# ardustatversion10.net
KiCad netlist of a schematic drawn in EAGLE
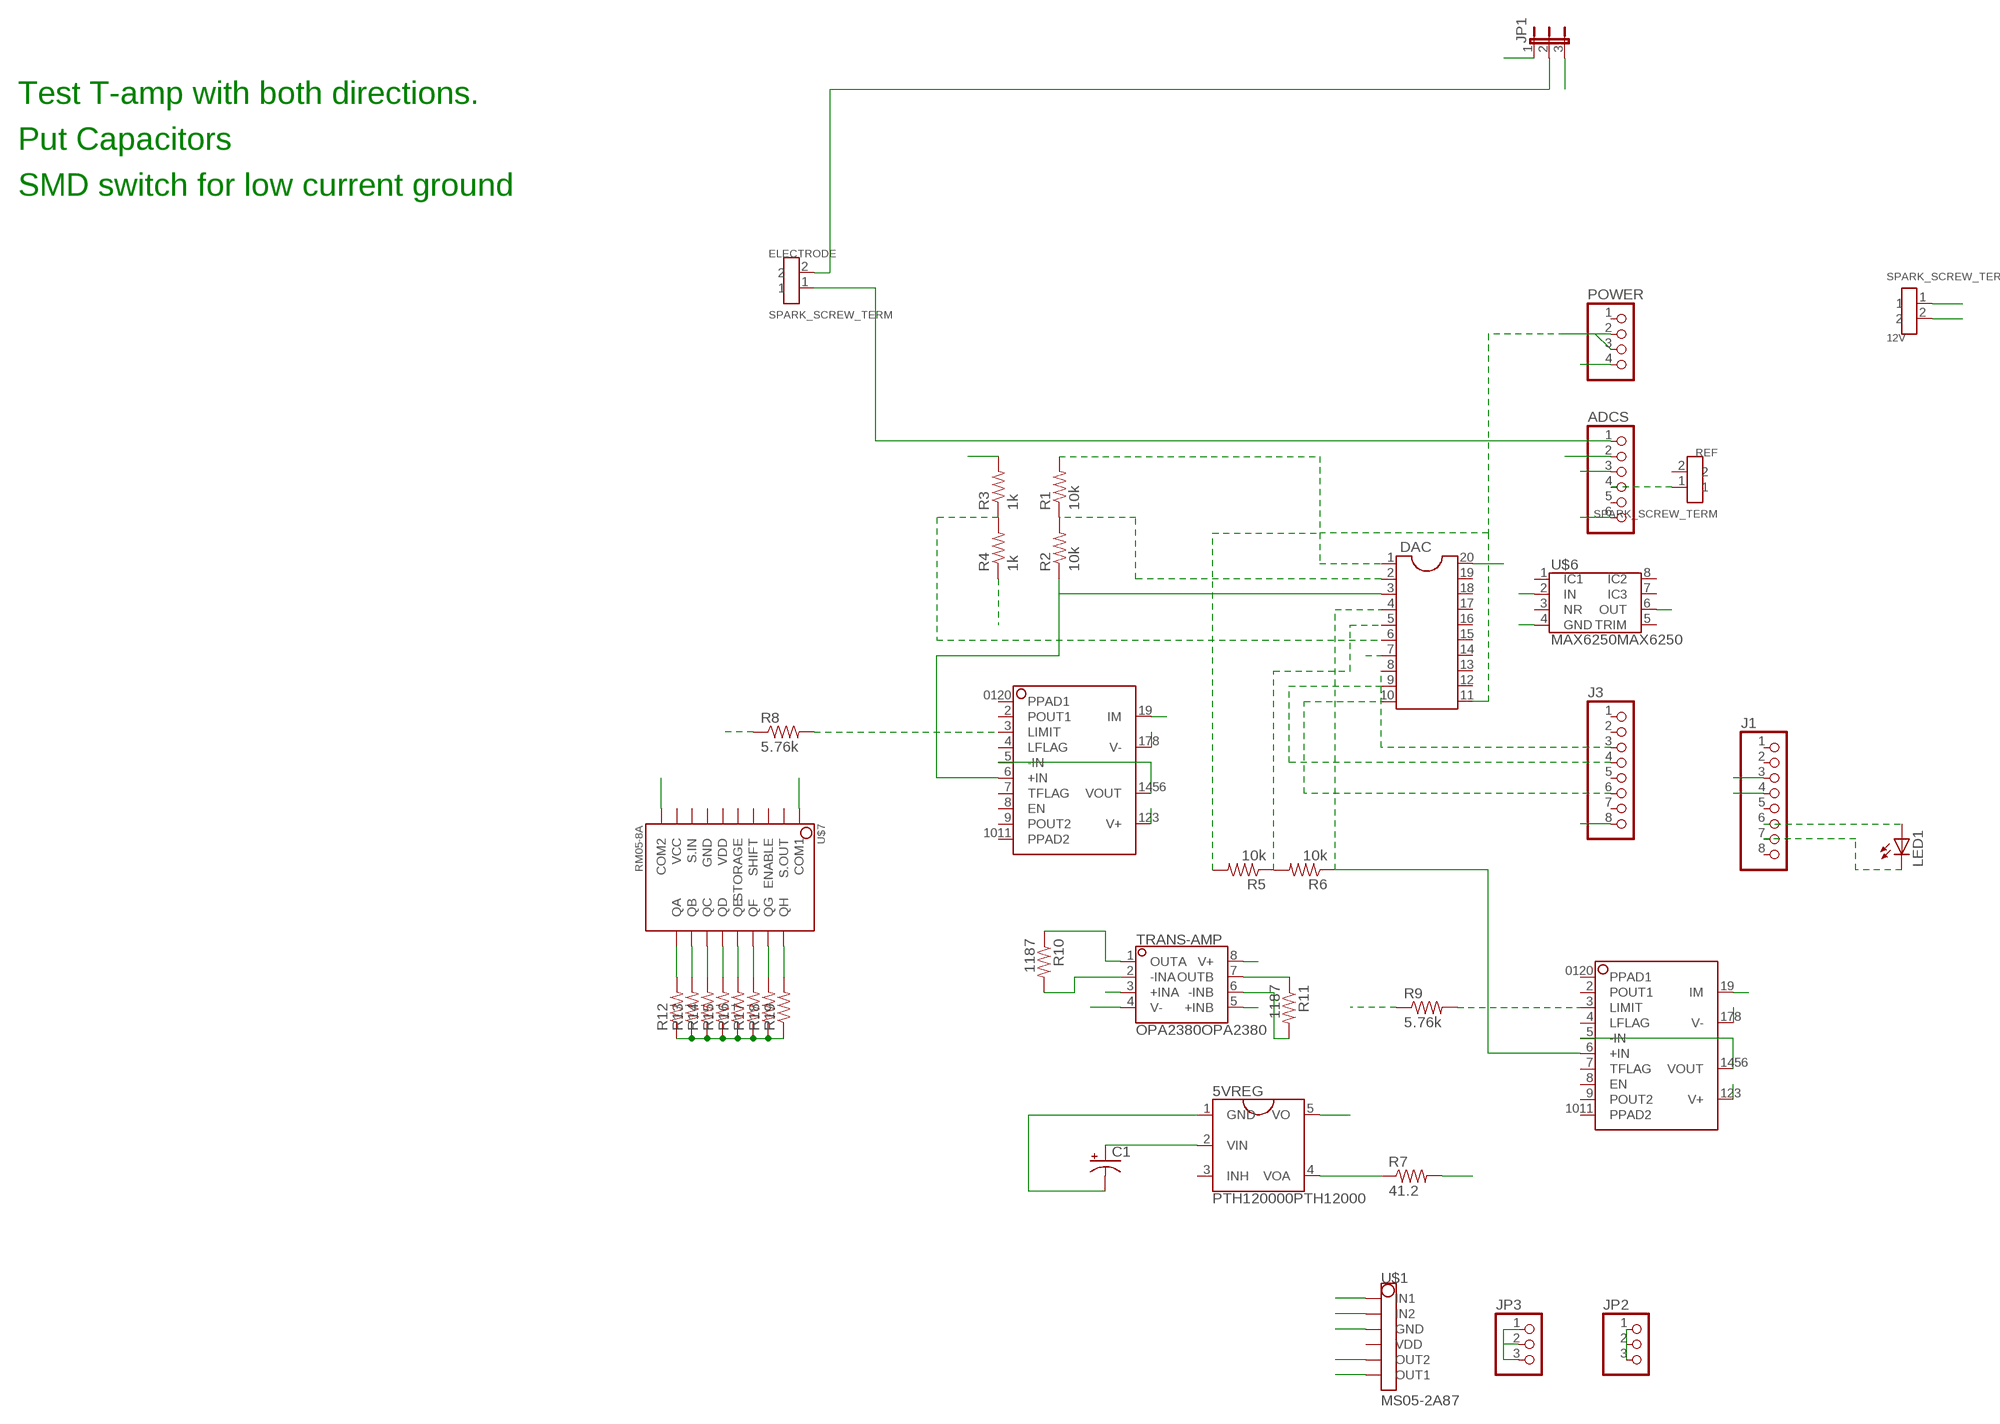
[diagram p0: schematic, sheet 1]

(export (version "E")
  (design (tool "Eeschema 10.0.6"))
  (components
    (comp (ref "5VREG")
      (value "PTH120000PTH12000")
      (footprint "eagle-import:PTH120000")
      (libsource (lib "eagle-import") (part "PTH120000PTH12000"))
    )
    (comp (ref "12V")
      (value "SPARK_SCREW_TERM")
      (footprint "eagle-import:SPARK_SCREW_TERM")
      (libsource (lib "eagle-import") (part "SPARK_SCREW_TERM"))
    )
    (comp (ref "ADCS")
      (value "PINHD-1X6")
      (footprint "eagle-import:1X06")
      (libsource (lib "eagle-import") (part "PINHD-1X6"))
    )
    (comp (ref "C1")
      (value "CPOL-USE5-10.5")
      (footprint "eagle-import:E5-10,5")
      (libsource (lib "eagle-import") (part "CPOL-USE5-10.5"))
    )
    (comp (ref "DAC")
      (value "DIL20S")
      (footprint "eagle-import:SOCKED-20")
      (libsource (lib "eagle-import") (part "DIL20S"))
    )
    (comp (ref "ELECTRODE")
      (value "SPARK_SCREW_TERM")
      (footprint "eagle-import:SPARK_SCREW_TERM")
      (libsource (lib "eagle-import") (part "SPARK_SCREW_TERM"))
    )
    (comp (ref "J1")
      (value "PINHD-1X8")
      (footprint "eagle-import:1X08")
      (libsource (lib "eagle-import") (part "PINHD-1X8"))
    )
    (comp (ref "J3")
      (value "PINHD-1X8")
      (footprint "eagle-import:1X08")
      (libsource (lib "eagle-import") (part "PINHD-1X8"))
    )
    (comp (ref "JP1")
      (value "JP2E")
      (footprint "eagle-import:JP2")
      (libsource (lib "eagle-import") (part "JP2E"))
    )
    (comp (ref "JP2")
      (value "PINHD-1X3")
      (footprint "eagle-import:1X03")
      (libsource (lib "eagle-import") (part "PINHD-1X3"))
    )
    (comp (ref "JP3")
      (value "PINHD-1X3")
      (footprint "eagle-import:1X03")
      (libsource (lib "eagle-import") (part "PINHD-1X3"))
    )
    (comp (ref "LED1")
      (value "LED5MM")
      (footprint "eagle-import:LED5MM")
      (libsource (lib "eagle-import") (part "LED5MM"))
    )
    (comp (ref "POWER")
      (value "PINHD-1X4")
      (footprint "eagle-import:1X04")
      (libsource (lib "eagle-import") (part "PINHD-1X4"))
    )
    (comp (ref "R1")
      (value "10k")
      (footprint "eagle-import:R1206")
      (libsource (lib "eagle-import") (part "R-US_R1206"))
    )
    (comp (ref "R2")
      (value "10k")
      (footprint "eagle-import:R1206")
      (libsource (lib "eagle-import") (part "resistor_R-US_R1206"))
    )
    (comp (ref "R3")
      (value "1k")
      (footprint "eagle-import:R1206")
      (libsource (lib "eagle-import") (part "R-US_R1206"))
    )
    (comp (ref "R4")
      (value "1k")
      (footprint "eagle-import:R1206")
      (libsource (lib "eagle-import") (part "R-US_R1206"))
    )
    (comp (ref "R5")
      (value "10k")
      (footprint "eagle-import:R1206")
      (libsource (lib "eagle-import") (part "R-US_R1206"))
    )
    (comp (ref "R6")
      (value "10k")
      (footprint "eagle-import:R1206")
      (libsource (lib "eagle-import") (part "R-US_R1206"))
    )
    (comp (ref "R7")
      (value "41.2")
      (footprint "eagle-import:M1206")
      (libsource (lib "eagle-import") (part "R-US_M1206"))
    )
    (comp (ref "R8")
      (value "5.76k")
      (footprint "eagle-import:R1206")
      (libsource (lib "eagle-import") (part "R-US_R1206"))
    )
    (comp (ref "R9")
      (value "5.76k")
      (footprint "eagle-import:M1206")
      (libsource (lib "eagle-import") (part "R-US_M1206"))
    )
    (comp (ref "R10")
      (value "1187")
      (footprint "eagle-import:M1206")
      (libsource (lib "eagle-import") (part "R-US_M1206"))
    )
    (comp (ref "R11")
      (value "1187")
      (footprint "eagle-import:M1206")
      (libsource (lib "eagle-import") (part "R-US_M1206"))
    )
    (comp (ref "R12")
      (value "R-US_0207/12")
      (footprint "eagle-import:0207_12")
      (libsource (lib "eagle-import") (part "resistor_R-US_0207/12"))
    )
    (comp (ref "R13")
      (value "R-US_0207/12")
      (footprint "eagle-import:0207_12")
      (libsource (lib "eagle-import") (part "resistor_R-US_0207/12"))
    )
    (comp (ref "R14")
      (value "R-US_0207/12")
      (footprint "eagle-import:0207_12")
      (libsource (lib "eagle-import") (part "resistor_R-US_0207/12"))
    )
    (comp (ref "R15")
      (value "R-US_0207/12")
      (footprint "eagle-import:0207_12")
      (libsource (lib "eagle-import") (part "resistor_R-US_0207/12"))
    )
    (comp (ref "R16")
      (value "R-US_0207/12")
      (footprint "eagle-import:0207_12")
      (libsource (lib "eagle-import") (part "resistor_R-US_0207/12"))
    )
    (comp (ref "R17")
      (value "R-US_0207/12")
      (footprint "eagle-import:0207_12")
      (libsource (lib "eagle-import") (part "resistor_R-US_0207/12"))
    )
    (comp (ref "R18")
      (value "R-US_0207/12")
      (footprint "eagle-import:0207_12")
      (libsource (lib "eagle-import") (part "resistor_R-US_0207/12"))
    )
    (comp (ref "R19")
      (value "R-US_0207/12")
      (footprint "eagle-import:0207_12")
      (libsource (lib "eagle-import") (part "resistor_R-US_0207/12"))
    )
    (comp (ref "REF")
      (value "SPARK_SCREW_TERM")
      (footprint "eagle-import:SPARK_SCREW_TERM")
      (libsource (lib "eagle-import") (part "SPARK_SCREW_TERM"))
    )
    (comp (ref "TRANS-AMP")
      (value "OPA2380OPA2380")
      (footprint "eagle-import:OPA2380")
      (libsource (lib "eagle-import") (part "OPA2380OPA2380"))
    )
    (comp (ref "U$1")
      (value "MS05-2A87")
      (footprint "eagle-import:MS05-2A87")
      (libsource (lib "eagle-import") (part "MS05-2A87"))
    )
    (comp (ref "U$3")
      (value "OPA569OPA569")
      (footprint "eagle-import:OPA569")
      (libsource (lib "eagle-import") (part "OPA569OPA569"))
    )
    (comp (ref "U$4")
      (value "OPA569OPA569")
      (footprint "eagle-import:OPA569")
      (libsource (lib "eagle-import") (part "OPA569OPA569"))
    )
    (comp (ref "U$6")
      (value "MAX6250MAX6250")
      (footprint "eagle-import:MAX6250")
      (libsource (lib "eagle-import") (part "MAX6250MAX6250"))
    )
    (comp (ref "U$7")
      (value "RM05-8A")
      (footprint "eagle-import:RM05-8A")
      (libsource (lib "eagle-import") (part "RM05-8A"))
    )
  )
  (nets
    (net (code "1") (name "/GND") (class "Default")
      (node (ref "12V") (pin "2") (pinfunction "2_2") (pintype "bidirectional"))
      (node (ref "5VREG") (pin "1") (pinfunction "GND_1") (pintype "power_in"))
      (node (ref "C1") (pin "-") (pinfunction "-_-") (pintype "passive"))
      (node (ref "DAC") (pin "1") (pinfunction "1_1") (pintype "passive"))
      (node (ref "DAC") (pin "11") (pinfunction "11_11") (pintype "passive"))
      (node (ref "JP1") (pin "3") (pinfunction "3_3") (pintype "passive"))
      (node (ref "POWER") (pin "2") (pinfunction "2_2") (pintype "passive"))
      (node (ref "POWER") (pin "3") (pinfunction "3_3") (pintype "passive"))
      (node (ref "R1") (pin "2") (pinfunction "2_2") (pintype "passive"))
      (node (ref "R4") (pin "1") (pinfunction "1_1") (pintype "passive"))
      (node (ref "R5") (pin "2") (pinfunction "2_2") (pintype "passive"))
      (node (ref "R7") (pin "2") (pinfunction "2_2") (pintype "passive"))
      (node (ref "R8") (pin "1") (pinfunction "1_1") (pintype "passive"))
      (node (ref "R9") (pin "1") (pinfunction "1_1") (pintype "passive"))
      (node (ref "TRANS-AMP") (pin "4") (pinfunction "V-_4") (pintype "power_in"))
      (node (ref "U$1") (pin "P$3") (pinfunction "GND_P$3") (pintype "bidirectional"))
      (node (ref "U$3") (pin "178") (pinfunction "V-_178") (pintype "bidirectional"))
      (node (ref "U$4") (pin "178") (pinfunction "V-_178") (pintype "bidirectional"))
      (node (ref "U$6") (pin "4") (pinfunction "GND_4") (pintype "bidirectional"))
    )
    (net (code "2") (name "/N$5") (class "Default")
      (node (ref "DAC") (pin "7") (pinfunction "7_7") (pintype "passive"))
      (node (ref "J1") (pin "3") (pinfunction "3_3") (pintype "passive"))
    )
    (net (code "3") (name "/N$8") (class "Default")
      (node (ref "ADCS") (pin "1") (pinfunction "1_1") (pintype "passive"))
      (node (ref "ELECTRODE") (pin "1") (pinfunction "1_1") (pintype "bidirectional"))
      (node (ref "JP2") (pin "1") (pinfunction "1_1") (pintype "passive"))
      (node (ref "JP2") (pin "2") (pinfunction "2_2") (pintype "passive"))
      (node (ref "JP2") (pin "3") (pinfunction "3_3") (pintype "passive"))
      (node (ref "R12") (pin "1") (pinfunction "1_1") (pintype "passive"))
      (node (ref "R13") (pin "1") (pinfunction "1_1") (pintype "passive"))
      (node (ref "R14") (pin "1") (pinfunction "1_1") (pintype "passive"))
      (node (ref "R15") (pin "1") (pinfunction "1_1") (pintype "passive"))
      (node (ref "R16") (pin "1") (pinfunction "1_1") (pintype "passive"))
      (node (ref "R17") (pin "1") (pinfunction "1_1") (pintype "passive"))
      (node (ref "R18") (pin "1") (pinfunction "1_1") (pintype "passive"))
      (node (ref "R19") (pin "1") (pinfunction "1_1") (pintype "passive"))
    )
    (net (code "4") (name "/N$9") (class "Default")
      (node (ref "U$1") (pin "P$2") (pinfunction "IN2_P$2") (pintype "bidirectional"))
      (node (ref "U$4") (pin "1456") (pinfunction "VOUT_1456") (pintype "bidirectional"))
      (node (ref "U$4") (pin "5") (pinfunction "-IN_5") (pintype "bidirectional"))
    )
    (net (code "5") (name "/N$10") (class "Default")
      (node (ref "R10") (pin "2") (pinfunction "2_2") (pintype "passive"))
      (node (ref "TRANS-AMP") (pin "2") (pinfunction "-INA_2") (pintype "input"))
      (node (ref "U$3") (pin "19") (pinfunction "IM_19") (pintype "bidirectional"))
    )
    (net (code "6") (name "/N$15") (class "Default")
      (node (ref "ADCS") (pin "2") (pinfunction "2_2") (pintype "passive"))
      (node (ref "DAC") (pin "3") (pinfunction "3_3") (pintype "passive"))
      (node (ref "R2") (pin "1") (pinfunction "1_1") (pintype "passive"))
      (node (ref "U$3") (pin "6") (pinfunction "+IN_6") (pintype "bidirectional"))
      (node (ref "U$7") (pin "P$1") (pinfunction "COM1_P$1") (pintype "bidirectional"))
      (node (ref "U$7") (pin "P$10") (pinfunction "COM2_P$10") (pintype "bidirectional"))
    )
    (net (code "7") (name "/N$19") (class "Default")
      (node (ref "5VREG") (pin "5") (pinfunction "VO_5") (pintype "bidirectional"))
      (node (ref "DAC") (pin "20") (pinfunction "20_20") (pintype "passive"))
      (node (ref "TRANS-AMP") (pin "8") (pinfunction "V+_8") (pintype "power_in"))
      (node (ref "U$3") (pin "123") (pinfunction "V+_123") (pintype "bidirectional"))
      (node (ref "U$4") (pin "123") (pinfunction "V+_123") (pintype "bidirectional"))
    )
    (net (code "8") (name "/N$21") (class "Default")
      (node (ref "ADCS") (pin "3") (pinfunction "3_3") (pintype "passive"))
      (node (ref "ELECTRODE") (pin "2") (pinfunction "2_2") (pintype "bidirectional"))
      (node (ref "JP1") (pin "2") (pinfunction "2_2") (pintype "passive"))
    )
    (net (code "9") (name "/N$22") (class "Default")
      (node (ref "12V") (pin "1") (pinfunction "1_1") (pintype "bidirectional"))
      (node (ref "5VREG") (pin "2") (pinfunction "VIN_2") (pintype "power_in"))
      (node (ref "C1") (pin "+") (pinfunction "+_+") (pintype "passive"))
      (node (ref "POWER") (pin "4") (pinfunction "4_4") (pintype "passive"))
      (node (ref "U$6") (pin "2") (pinfunction "IN_2") (pintype "bidirectional"))
    )
    (net (code "10") (name "/N$23") (class "Default")
      (node (ref "JP3") (pin "1") (pinfunction "1_1") (pintype "passive"))
      (node (ref "JP3") (pin "2") (pinfunction "2_2") (pintype "passive"))
      (node (ref "JP3") (pin "3") (pinfunction "3_3") (pintype "passive"))
      (node (ref "U$1") (pin "P$6") (pinfunction "OUT1_P$6") (pintype "bidirectional"))
    )
    (net (code "11") (name "/N$24") (class "Default")
      (node (ref "J3") (pin "8") (pinfunction "8_8") (pintype "passive"))
      (node (ref "R3") (pin "2") (pinfunction "2_2") (pintype "passive"))
      (node (ref "TRANS-AMP") (pin "3") (pinfunction "+INA_3") (pintype "input"))
      (node (ref "TRANS-AMP") (pin "5") (pinfunction "+INB_5") (pintype "input"))
      (node (ref "U$6") (pin "6") (pinfunction "OUT_6") (pintype "bidirectional"))
    )
    (net (code "12") (name "/N$26") (class "Default")
      (node (ref "U$1") (pin "P$1") (pinfunction "IN1_P$1") (pintype "bidirectional"))
      (node (ref "U$3") (pin "1456") (pinfunction "VOUT_1456") (pintype "bidirectional"))
      (node (ref "U$3") (pin "5") (pinfunction "-IN_5") (pintype "bidirectional"))
    )
    (net (code "13") (name "/N$36") (class "Default")
      (node (ref "JP1") (pin "1") (pinfunction "1_1") (pintype "passive"))
      (node (ref "U$1") (pin "P$5") (pinfunction "OUT2_P$5") (pintype "bidirectional"))
    )
    (net (code "14") (name "/N$48") (class "Default")
      (node (ref "ADCS") (pin "6") (pinfunction "6_6") (pintype "passive"))
      (node (ref "R11") (pin "1") (pinfunction "1_1") (pintype "passive"))
      (node (ref "TRANS-AMP") (pin "7") (pinfunction "OUTB_7") (pintype "output"))
    )
    (net (code "15") (name "/N$49") (class "Default")
      (node (ref "R11") (pin "2") (pinfunction "2_2") (pintype "passive"))
      (node (ref "TRANS-AMP") (pin "6") (pinfunction "-INB_6") (pintype "input"))
      (node (ref "U$4") (pin "19") (pinfunction "IM_19") (pintype "bidirectional"))
    )
    (net (code "16") (name "Net-(5VREG-VOA)") (class "Default")
      (node (ref "5VREG") (pin "4") (pinfunction "VOA_4") (pintype "input"))
      (node (ref "R7") (pin "1") (pinfunction "1_1") (pintype "passive"))
    )
    (net (code "17") (name "Net-(ADCS-Pad4)") (class "Default")
      (node (ref "ADCS") (pin "4") (pinfunction "4_4") (pintype "passive"))
      (node (ref "REF") (pin "1") (pinfunction "1_1") (pintype "bidirectional"))
    )
    (net (code "18") (name "Net-(DAC-Pad2)") (class "Default")
      (node (ref "DAC") (pin "2") (pinfunction "2_2") (pintype "passive"))
      (node (ref "R1") (pin "1") (pinfunction "1_1") (pintype "passive"))
      (node (ref "R2") (pin "2") (pinfunction "2_2") (pintype "passive"))
    )
    (net (code "19") (name "Net-(DAC-Pad5)") (class "Default")
      (node (ref "DAC") (pin "5") (pinfunction "5_5") (pintype "passive"))
      (node (ref "R5") (pin "1") (pinfunction "1_1") (pintype "passive"))
      (node (ref "R6") (pin "2") (pinfunction "2_2") (pintype "passive"))
    )
    (net (code "20") (name "Net-(DAC-Pad6)") (class "Default")
      (node (ref "DAC") (pin "6") (pinfunction "6_6") (pintype "passive"))
      (node (ref "R3") (pin "1") (pinfunction "1_1") (pintype "passive"))
      (node (ref "R4") (pin "2") (pinfunction "2_2") (pintype "passive"))
    )
    (net (code "21") (name "Net-(DAC-Pad8)") (class "Default")
      (node (ref "DAC") (pin "8") (pinfunction "8_8") (pintype "passive"))
      (node (ref "J3") (pin "3") (pinfunction "3_3") (pintype "passive"))
    )
    (net (code "22") (name "Net-(DAC-Pad9)") (class "Default")
      (node (ref "DAC") (pin "9") (pinfunction "9_9") (pintype "passive"))
      (node (ref "J3") (pin "4") (pinfunction "4_4") (pintype "passive"))
    )
    (net (code "23") (name "Net-(DAC-Pad10)") (class "Default")
      (node (ref "DAC") (pin "10") (pinfunction "10_10") (pintype "passive"))
      (node (ref "J3") (pin "6") (pinfunction "6_6") (pintype "passive"))
    )
    (net (code "24") (name "Net-(J1-Pad6)") (class "Default")
      (node (ref "J1") (pin "6") (pinfunction "6_6") (pintype "passive"))
      (node (ref "LED1") (pin "A") (pinfunction "A_A") (pintype "passive"))
    )
    (net (code "25") (name "Net-(LED1-C)") (class "Default")
      (node (ref "J1") (pin "7") (pinfunction "7_7") (pintype "passive"))
      (node (ref "LED1") (pin "K") (pinfunction "C_K") (pintype "passive"))
    )
    (net (code "26") (name "Net-(TRANS-AMP-OUTA)") (class "Default")
      (node (ref "R10") (pin "1") (pinfunction "1_1") (pintype "passive"))
      (node (ref "TRANS-AMP") (pin "1") (pinfunction "OUTA_1") (pintype "output"))
    )
    (net (code "27") (name "Net-(U$3-LIMIT)") (class "Default")
      (node (ref "R8") (pin "2") (pinfunction "2_2") (pintype "passive"))
      (node (ref "U$3") (pin "3") (pinfunction "LIMIT_3") (pintype "bidirectional"))
    )
    (net (code "28") (name "Net-(U$4-+IN)") (class "Default")
      (node (ref "DAC") (pin "4") (pinfunction "4_4") (pintype "passive"))
      (node (ref "R6") (pin "1") (pinfunction "1_1") (pintype "passive"))
      (node (ref "U$4") (pin "6") (pinfunction "+IN_6") (pintype "bidirectional"))
    )
    (net (code "29") (name "Net-(U$4-LIMIT)") (class "Default")
      (node (ref "R9") (pin "2") (pinfunction "2_2") (pintype "passive"))
      (node (ref "U$4") (pin "3") (pinfunction "LIMIT_3") (pintype "bidirectional"))
    )
    (net (code "30") (name "Net-(U$7-QA)") (class "Default")
      (node (ref "R12") (pin "2") (pinfunction "2_2") (pintype "passive"))
      (node (ref "U$7") (pin "P$11") (pinfunction "QA_P$11") (pintype "bidirectional"))
    )
    (net (code "31") (name "Net-(U$7-QB)") (class "Default")
      (node (ref "R13") (pin "2") (pinfunction "2_2") (pintype "passive"))
      (node (ref "U$7") (pin "P$12") (pinfunction "QB_P$12") (pintype "bidirectional"))
    )
    (net (code "32") (name "Net-(U$7-QC)") (class "Default")
      (node (ref "R14") (pin "2") (pinfunction "2_2") (pintype "passive"))
      (node (ref "U$7") (pin "P$13") (pinfunction "QC_P$13") (pintype "bidirectional"))
    )
    (net (code "33") (name "Net-(U$7-QD)") (class "Default")
      (node (ref "R15") (pin "2") (pinfunction "2_2") (pintype "passive"))
      (node (ref "U$7") (pin "P$14") (pinfunction "QD_P$14") (pintype "bidirectional"))
    )
    (net (code "34") (name "Net-(U$7-QE)") (class "Default")
      (node (ref "R16") (pin "2") (pinfunction "2_2") (pintype "passive"))
      (node (ref "U$7") (pin "P$15") (pinfunction "QE_P$15") (pintype "bidirectional"))
    )
    (net (code "35") (name "Net-(U$7-QF)") (class "Default")
      (node (ref "R17") (pin "2") (pinfunction "2_2") (pintype "passive"))
      (node (ref "U$7") (pin "P$16") (pinfunction "QF_P$16") (pintype "bidirectional"))
    )
    (net (code "36") (name "Net-(U$7-QG)") (class "Default")
      (node (ref "R18") (pin "2") (pinfunction "2_2") (pintype "passive"))
      (node (ref "U$7") (pin "P$17") (pinfunction "QG_P$17") (pintype "bidirectional"))
    )
    (net (code "37") (name "Net-(U$7-QH)") (class "Default")
      (node (ref "R19") (pin "2") (pinfunction "2_2") (pintype "passive"))
      (node (ref "U$7") (pin "P$18") (pinfunction "QH_P$18") (pintype "bidirectional"))
    )
    (net (code "38") (name "unconnected-(5VREG-INH-Pad3)") (class "Default")
      (node (ref "5VREG") (pin "3") (pinfunction "INH_3") (pintype "input"))
    )
    (net (code "39") (name "unconnected-(ADCS-Pad5)") (class "Default")
      (node (ref "ADCS") (pin "5") (pinfunction "5_5") (pintype "passive"))
    )
    (net (code "40") (name "unconnected-(DAC-Pad12)") (class "Default")
      (node (ref "DAC") (pin "12") (pinfunction "12_12") (pintype "passive"))
    )
    (net (code "41") (name "unconnected-(DAC-Pad13)") (class "Default")
      (node (ref "DAC") (pin "13") (pinfunction "13_13") (pintype "passive"))
    )
    (net (code "42") (name "unconnected-(DAC-Pad14)") (class "Default")
      (node (ref "DAC") (pin "14") (pinfunction "14_14") (pintype "passive"))
    )
    (net (code "43") (name "unconnected-(DAC-Pad15)") (class "Default")
      (node (ref "DAC") (pin "15") (pinfunction "15_15") (pintype "passive"))
    )
    (net (code "44") (name "unconnected-(DAC-Pad16)") (class "Default")
      (node (ref "DAC") (pin "16") (pinfunction "16_16") (pintype "passive"))
    )
    (net (code "45") (name "unconnected-(DAC-Pad17)") (class "Default")
      (node (ref "DAC") (pin "17") (pinfunction "17_17") (pintype "passive"))
    )
    (net (code "46") (name "unconnected-(DAC-Pad18)") (class "Default")
      (node (ref "DAC") (pin "18") (pinfunction "18_18") (pintype "passive"))
    )
    (net (code "47") (name "unconnected-(DAC-Pad19)") (class "Default")
      (node (ref "DAC") (pin "19") (pinfunction "19_19") (pintype "passive"))
    )
    (net (code "48") (name "unconnected-(J1-Pad1)") (class "Default")
      (node (ref "J1") (pin "1") (pinfunction "1_1") (pintype "passive"))
    )
    (net (code "49") (name "unconnected-(J1-Pad2)") (class "Default")
      (node (ref "J1") (pin "2") (pinfunction "2_2") (pintype "passive"))
    )
    (net (code "50") (name "unconnected-(J1-Pad4)") (class "Default")
      (node (ref "J1") (pin "4") (pinfunction "4_4") (pintype "passive"))
    )
    (net (code "51") (name "unconnected-(J1-Pad5)") (class "Default")
      (node (ref "J1") (pin "5") (pinfunction "5_5") (pintype "passive"))
    )
    (net (code "52") (name "unconnected-(J1-Pad8)") (class "Default")
      (node (ref "J1") (pin "8") (pinfunction "8_8") (pintype "passive"))
    )
    (net (code "53") (name "unconnected-(J3-Pad1)") (class "Default")
      (node (ref "J3") (pin "1") (pinfunction "1_1") (pintype "passive"))
    )
    (net (code "54") (name "unconnected-(J3-Pad2)") (class "Default")
      (node (ref "J3") (pin "2") (pinfunction "2_2") (pintype "passive"))
    )
    (net (code "55") (name "unconnected-(J3-Pad5)") (class "Default")
      (node (ref "J3") (pin "5") (pinfunction "5_5") (pintype "passive"))
    )
    (net (code "56") (name "unconnected-(J3-Pad7)") (class "Default")
      (node (ref "J3") (pin "7") (pinfunction "7_7") (pintype "passive"))
    )
    (net (code "57") (name "unconnected-(POWER-Pad1)") (class "Default")
      (node (ref "POWER") (pin "1") (pinfunction "1_1") (pintype "passive"))
    )
    (net (code "58") (name "unconnected-(REF-Pad2)") (class "Default")
      (node (ref "REF") (pin "2") (pinfunction "2_2") (pintype "bidirectional"))
    )
    (net (code "59") (name "unconnected-(U$1-VDD-PadP$4)") (class "Default")
      (node (ref "U$1") (pin "P$4") (pinfunction "VDD_P$4") (pintype "bidirectional"))
    )
    (net (code "60") (name "unconnected-(U$3-EN-Pad8)") (class "Default")
      (node (ref "U$3") (pin "8") (pinfunction "EN_8") (pintype "bidirectional"))
    )
    (net (code "61") (name "unconnected-(U$3-LFLAG-Pad4)") (class "Default")
      (node (ref "U$3") (pin "4") (pinfunction "LFLAG_4") (pintype "bidirectional"))
    )
    (net (code "62") (name "unconnected-(U$3-POUT1-Pad2)") (class "Default")
      (node (ref "U$3") (pin "2") (pinfunction "POUT1_2") (pintype "bidirectional"))
    )
    (net (code "63") (name "unconnected-(U$3-POUT2-Pad9)") (class "Default")
      (node (ref "U$3") (pin "9") (pinfunction "POUT2_9") (pintype "bidirectional"))
    )
    (net (code "64") (name "unconnected-(U$3-PPAD1-Pad0120)") (class "Default")
      (node (ref "U$3") (pin "0120") (pinfunction "PPAD1_0120") (pintype "bidirectional"))
    )
    (net (code "65") (name "unconnected-(U$3-PPAD2-Pad1011)") (class "Default")
      (node (ref "U$3") (pin "1011") (pinfunction "PPAD2_1011") (pintype "bidirectional"))
    )
    (net (code "66") (name "unconnected-(U$3-TFLAG-Pad7)") (class "Default")
      (node (ref "U$3") (pin "7") (pinfunction "TFLAG_7") (pintype "bidirectional"))
    )
    (net (code "67") (name "unconnected-(U$4-EN-Pad8)") (class "Default")
      (node (ref "U$4") (pin "8") (pinfunction "EN_8") (pintype "bidirectional"))
    )
    (net (code "68") (name "unconnected-(U$4-LFLAG-Pad4)") (class "Default")
      (node (ref "U$4") (pin "4") (pinfunction "LFLAG_4") (pintype "bidirectional"))
    )
    (net (code "69") (name "unconnected-(U$4-POUT1-Pad2)") (class "Default")
      (node (ref "U$4") (pin "2") (pinfunction "POUT1_2") (pintype "bidirectional"))
    )
    (net (code "70") (name "unconnected-(U$4-POUT2-Pad9)") (class "Default")
      (node (ref "U$4") (pin "9") (pinfunction "POUT2_9") (pintype "bidirectional"))
    )
    (net (code "71") (name "unconnected-(U$4-PPAD1-Pad0120)") (class "Default")
      (node (ref "U$4") (pin "0120") (pinfunction "PPAD1_0120") (pintype "bidirectional"))
    )
    (net (code "72") (name "unconnected-(U$4-PPAD2-Pad1011)") (class "Default")
      (node (ref "U$4") (pin "1011") (pinfunction "PPAD2_1011") (pintype "bidirectional"))
    )
    (net (code "73") (name "unconnected-(U$4-TFLAG-Pad7)") (class "Default")
      (node (ref "U$4") (pin "7") (pinfunction "TFLAG_7") (pintype "bidirectional"))
    )
    (net (code "74") (name "unconnected-(U$6-IC1-Pad1)") (class "Default")
      (node (ref "U$6") (pin "1") (pinfunction "IC1_1") (pintype "bidirectional"))
    )
    (net (code "75") (name "unconnected-(U$6-IC2-Pad8)") (class "Default")
      (node (ref "U$6") (pin "8") (pinfunction "IC2_8") (pintype "bidirectional"))
    )
    (net (code "76") (name "unconnected-(U$6-IC3-Pad7)") (class "Default")
      (node (ref "U$6") (pin "7") (pinfunction "IC3_7") (pintype "bidirectional"))
    )
    (net (code "77") (name "unconnected-(U$6-NR-Pad3)") (class "Default")
      (node (ref "U$6") (pin "3") (pinfunction "NR_3") (pintype "bidirectional"))
    )
    (net (code "78") (name "unconnected-(U$6-TRIM-Pad5)") (class "Default")
      (node (ref "U$6") (pin "5") (pinfunction "TRIM_5") (pintype "bidirectional"))
    )
    (net (code "79") (name "unconnected-(U$7-ENABLE-PadP$3)") (class "Default")
      (node (ref "U$7") (pin "P$3") (pinfunction "ENABLE_P$3") (pintype "bidirectional"))
    )
    (net (code "80") (name "unconnected-(U$7-GND-PadP$7)") (class "Default")
      (node (ref "U$7") (pin "P$7") (pinfunction "GND_P$7") (pintype "bidirectional"))
    )
    (net (code "81") (name "unconnected-(U$7-S.IN-PadP$8)") (class "Default")
      (node (ref "U$7") (pin "P$8") (pinfunction "S.IN_P$8") (pintype "bidirectional"))
    )
    (net (code "82") (name "unconnected-(U$7-S.OUT-PadP$2)") (class "Default")
      (node (ref "U$7") (pin "P$2") (pinfunction "S.OUT_P$2") (pintype "bidirectional"))
    )
    (net (code "83") (name "unconnected-(U$7-SHIFT-PadP$4)") (class "Default")
      (node (ref "U$7") (pin "P$4") (pinfunction "SHIFT_P$4") (pintype "bidirectional"))
    )
    (net (code "84") (name "unconnected-(U$7-STORAGE-PadP$5)") (class "Default")
      (node (ref "U$7") (pin "P$5") (pinfunction "STORAGE_P$5") (pintype "bidirectional"))
    )
    (net (code "85") (name "unconnected-(U$7-VCC-PadP$9)") (class "Default")
      (node (ref "U$7") (pin "P$9") (pinfunction "VCC_P$9") (pintype "bidirectional"))
    )
    (net (code "86") (name "unconnected-(U$7-VDD-PadP$6)") (class "Default")
      (node (ref "U$7") (pin "P$6") (pinfunction "VDD_P$6") (pintype "bidirectional"))
    )
  )
)
